# power_board1_v1_0.net
KiCad netlist of a schematic drawn in EAGLE
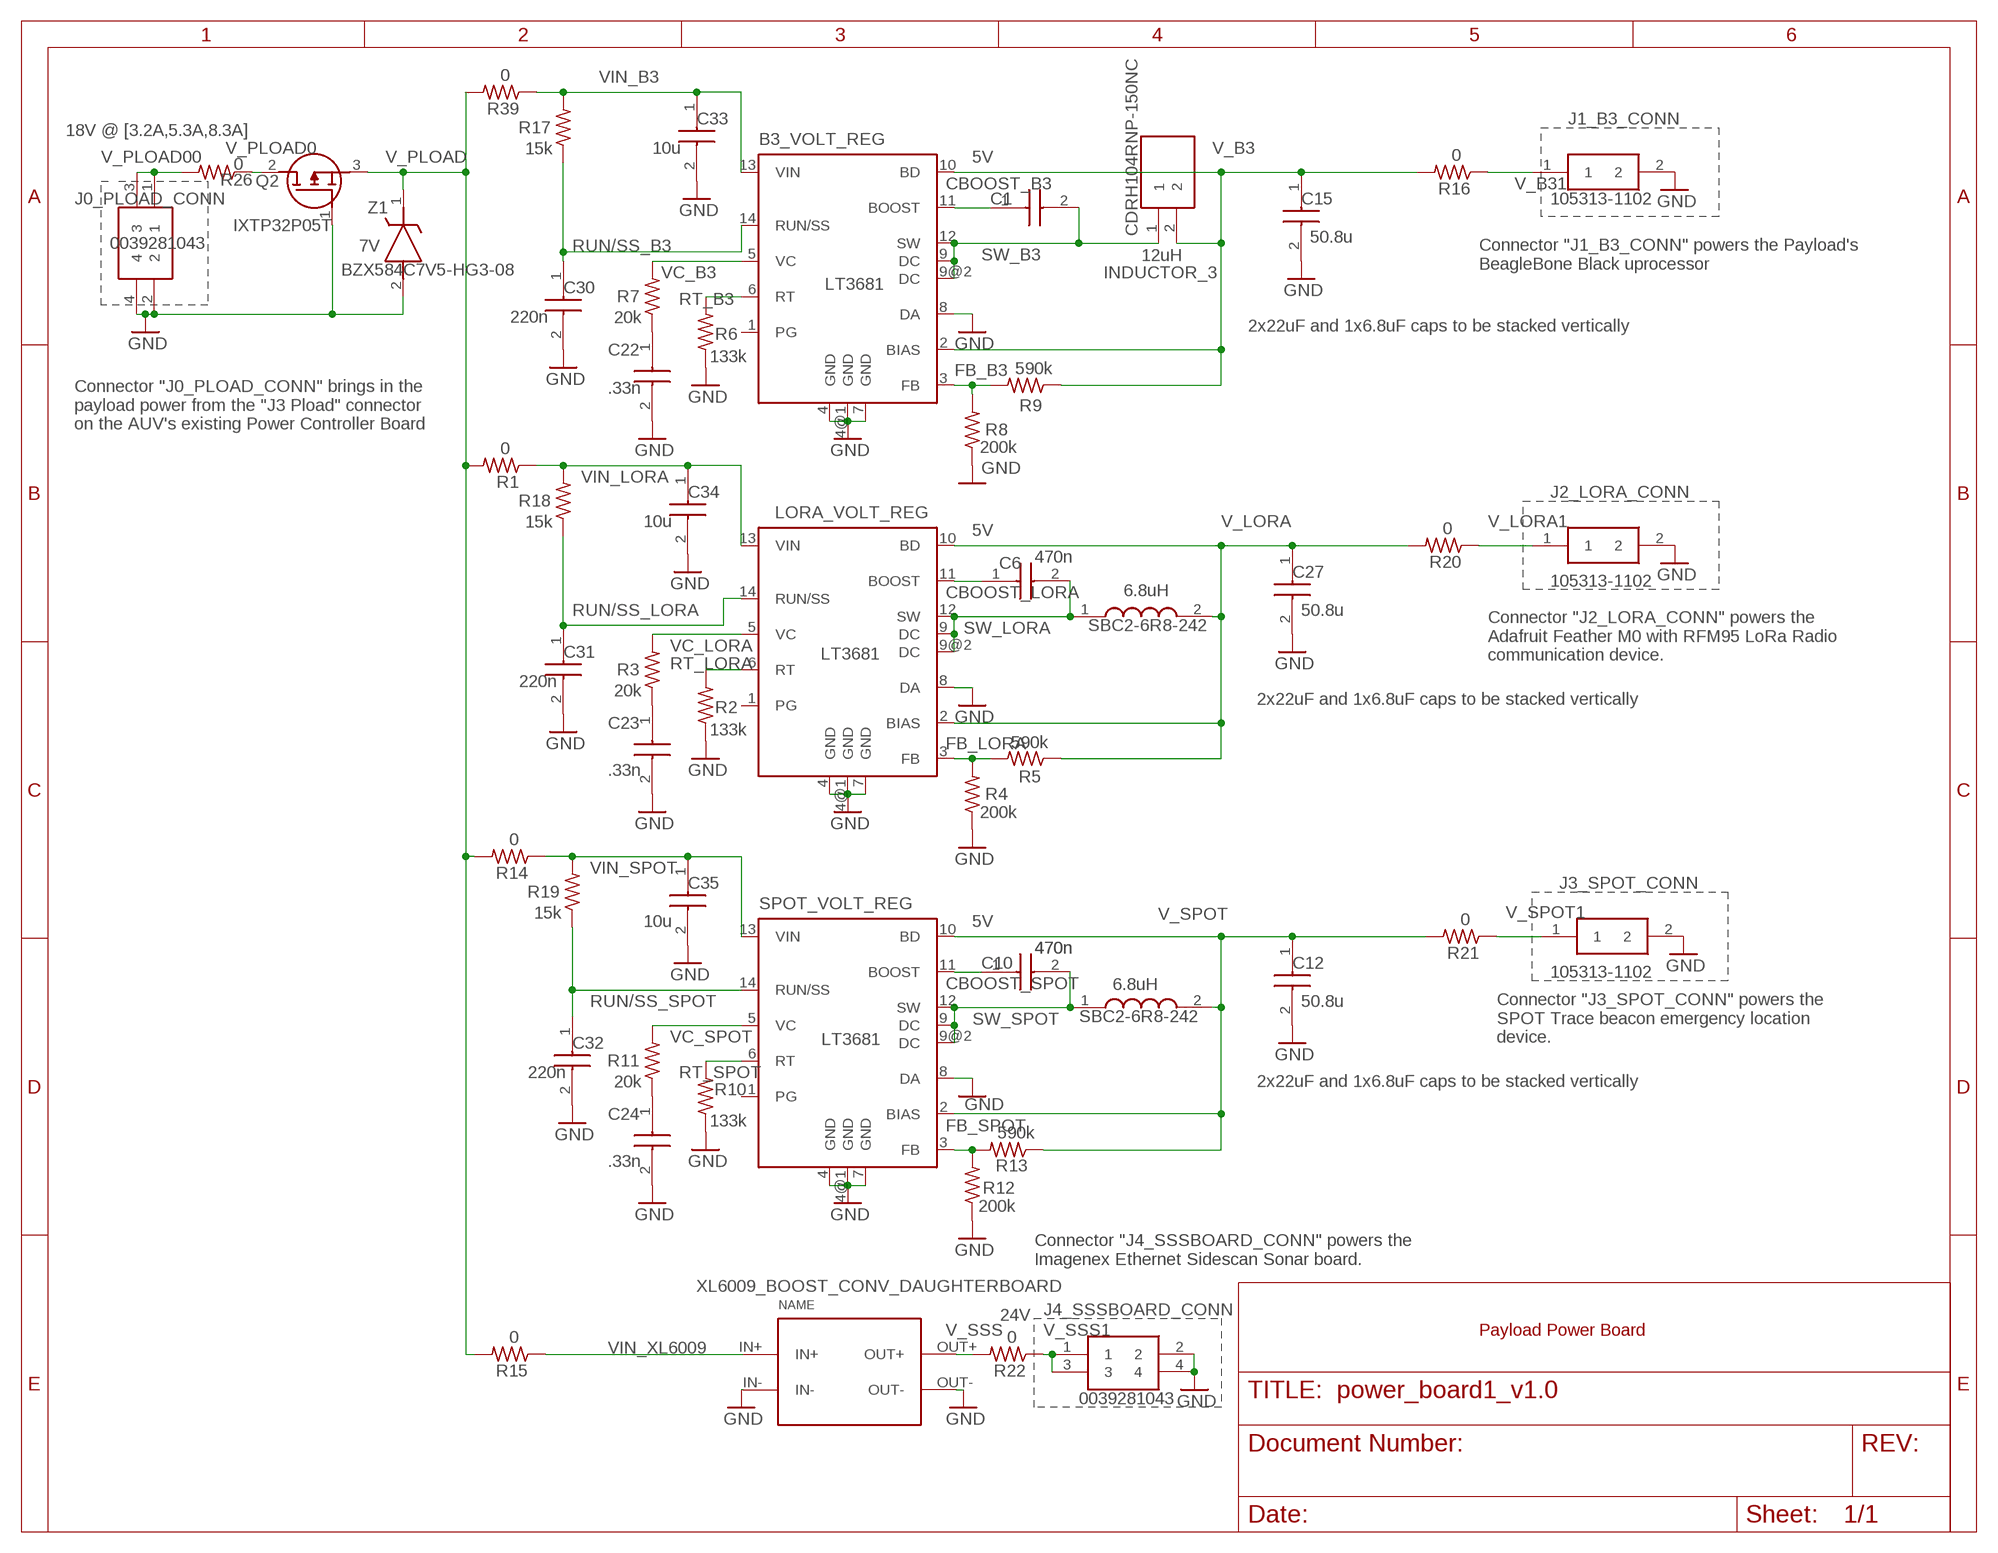
[diagram p0: schematic, sheet 1]

(export (version "E")
  (design (tool "Eeschema 10.0.6"))
  (components
    (comp (ref "B3_VOLT_REG")
      (value "LT3681")
      (footprint "eagle-import:DFN14-4X3DE")
      (fields (field (name "MPN") "LT3681EDE#PBF"))
      (libsource (lib "eagle-import") (part "LT3681"))
    )
    (comp (ref "C1")
      (value "08053C474KAT2A")
      (footprint "eagle-import:CAPC2012X140N")
      (fields
        (field (name "MOUSER_PART_NUMBER") "581-08053C474KAT2A")
        (field (name "RS_PART_NUMBER") "1747389")
      )
      (libsource (lib "eagle-import") (part "08053C474KAT2A"))
    )
    (comp (ref "C6")
      (value "08053C474KAT2A")
      (footprint "eagle-import:CAPC2012X140N")
      (fields
        (field (name "MOUSER_PART_NUMBER") "581-08053C474KAT2A")
        (field (name "RS_PART_NUMBER") "1747389")
      )
      (libsource (lib "eagle-import") (part "08053C474KAT2A"))
    )
    (comp (ref "C10")
      (value "08053C474KAT2A")
      (footprint "eagle-import:CAPC2012X140N")
      (fields
        (field (name "MOUSER_PART_NUMBER") "581-08053C474KAT2A")
        (field (name "RS_PART_NUMBER") "1747389")
      )
      (libsource (lib "eagle-import") (part "08053C474KAT2A"))
    )
    (comp (ref "C12")
      (value "12103C226KAT2A")
      (footprint "eagle-import:CAPC3225X279N")
      (fields (field (name "MOUSER_PART_NUMBER") "581-12103C226KAT2A"))
      (libsource (lib "eagle-import") (part "12103C226KAT2A"))
    )
    (comp (ref "C15")
      (value "12103C226KAT2A")
      (footprint "eagle-import:CAPC3225X279N")
      (fields (field (name "MOUSER_PART_NUMBER") "581-12103C226KAT2A"))
      (libsource (lib "eagle-import") (part "12103C226KAT2A"))
    )
    (comp (ref "C22")
      (value "08053C334KAT2A")
      (footprint "eagle-import:CAPC2012X140N")
      (fields
        (field (name "MOUSER_PART_NUMBER") "581-08053C334KAT2A")
        (field (name "RS_PART_NUMBER") "1747387")
      )
      (libsource (lib "eagle-import") (part "08053C334KAT2A"))
    )
    (comp (ref "C23")
      (value "08053C334KAT2A")
      (footprint "eagle-import:CAPC2012X140N")
      (fields
        (field (name "MOUSER_PART_NUMBER") "581-08053C334KAT2A")
        (field (name "RS_PART_NUMBER") "1747387")
      )
      (libsource (lib "eagle-import") (part "08053C334KAT2A"))
    )
    (comp (ref "C24")
      (value "08053C334KAT2A")
      (footprint "eagle-import:CAPC2012X140N")
      (fields
        (field (name "MOUSER_PART_NUMBER") "581-08053C334KAT2A")
        (field (name "RS_PART_NUMBER") "1747387")
      )
      (libsource (lib "eagle-import") (part "08053C334KAT2A"))
    )
    (comp (ref "C27")
      (value "12103C226KAT2A")
      (footprint "eagle-import:CAPC3225X279N")
      (fields (field (name "MOUSER_PART_NUMBER") "581-12103C226KAT2A"))
      (libsource (lib "eagle-import") (part "12103C226KAT2A"))
    )
    (comp (ref "C30")
      (value "08051C224KAT2A")
      (footprint "eagle-import:CAPC2012X140N")
      (fields (field (name "MOUSER_PART_NUMBER") "581-08051C224KAT2A"))
      (libsource (lib "eagle-import") (part "08051C224KAT2A"))
    )
    (comp (ref "C31")
      (value "08051C224KAT2A")
      (footprint "eagle-import:CAPC2012X140N")
      (fields (field (name "MOUSER_PART_NUMBER") "581-08051C224KAT2A"))
      (libsource (lib "eagle-import") (part "08051C224KAT2A"))
    )
    (comp (ref "C32")
      (value "08051C224KAT2A")
      (footprint "eagle-import:CAPC2012X140N")
      (fields (field (name "MOUSER_PART_NUMBER") "581-08051C224KAT2A"))
      (libsource (lib "eagle-import") (part "08051C224KAT2A"))
    )
    (comp (ref "C33")
      (value "22201C106KAT2A")
      (footprint "eagle-import:CAPC5750X279N")
      (fields (field (name "MOUSER_PART_NUMBER") "581-22201C106KAT2A"))
      (libsource (lib "eagle-import") (part "22201C106KAT2A"))
    )
    (comp (ref "C34")
      (value "22201C106KAT2A")
      (footprint "eagle-import:CAPC5750X279N")
      (fields (field (name "MOUSER_PART_NUMBER") "581-22201C106KAT2A"))
      (libsource (lib "eagle-import") (part "22201C106KAT2A"))
    )
    (comp (ref "C35")
      (value "22201C106KAT2A")
      (footprint "eagle-import:CAPC5750X279N")
      (fields (field (name "MOUSER_PART_NUMBER") "581-22201C106KAT2A"))
      (libsource (lib "eagle-import") (part "22201C106KAT2A"))
    )
    (comp (ref "INDUCTOR_3")
      (value "CDRH104RNP-150NC")
      (footprint "eagle-import:INDPM102100X400N")
      (fields (field (name "MOUSER_PART_NUMBER") "851-CDRH104RNP-150NC"))
      (libsource (lib "eagle-import") (part "CDRH104RNP-150NC"))
    )
    (comp (ref "J0_PLOAD_CONN")
      (value "0039281043")
      (footprint "eagle-import:SHDR4W125P550X420_2X2_960X960X")
      (libsource (lib "eagle-import") (part "0039281043"))
    )
    (comp (ref "J1_B3_CONN")
      (value "105313-1102")
      (footprint "eagle-import:1053131102")
      (fields (field (name "MOUSER_PART_NUMBER") "538-105313-1102") (field (name "RS_PART_NUMBER") "1623686"))
      (libsource (lib "eagle-import") (part "105313-1102"))
    )
    (comp (ref "J2_LORA_CONN")
      (value "105313-1102")
      (footprint "eagle-import:1053131102")
      (fields (field (name "MOUSER_PART_NUMBER") "538-105313-1102") (field (name "RS_PART_NUMBER") "1623686"))
      (libsource (lib "eagle-import") (part "105313-1102"))
    )
    (comp (ref "J3_SPOT_CONN")
      (value "105313-1102")
      (footprint "eagle-import:1053131102")
      (fields (field (name "MOUSER_PART_NUMBER") "538-105313-1102") (field (name "RS_PART_NUMBER") "1623686"))
      (libsource (lib "eagle-import") (part "105313-1102"))
    )
    (comp (ref "J4_SSSBOARD_CONN")
      (value "0039281043")
      (footprint "eagle-import:SHDR4W125P550X420_2X2_960X960X")
      (libsource (lib "eagle-import") (part "0039281043"))
    )
    (comp (ref "L4")
      (value "SBC2-6R8-242")
      (footprint "eagle-import:SBC26R8242")
      (fields (field (name "MOUSER_PART_NUMBER") "80-SBC2-6R8-242"))
      (libsource (lib "eagle-import") (part "SBC2-6R8-242"))
    )
    (comp (ref "L5")
      (value "SBC2-6R8-242")
      (footprint "eagle-import:SBC26R8242")
      (fields (field (name "MOUSER_PART_NUMBER") "80-SBC2-6R8-242"))
      (libsource (lib "eagle-import") (part "SBC2-6R8-242"))
    )
    (comp (ref "LORA_VOLT_REG")
      (value "LT3681")
      (footprint "eagle-import:DFN14-4X3DE")
      (fields (field (name "MPN") "LT3681EDE#PBF"))
      (libsource (lib "eagle-import") (part "LT3681"))
    )
    (comp (ref "Q2")
      (value "IXTP32P05T")
      (footprint "eagle-import:TO254P470X1001X2012-3P")
      (fields (field (name "MOUSER_PART_NUMBER") "747-IXTP32P05T"))
      (libsource (lib "eagle-import") (part "IXTP32P05T"))
    )
    (comp (ref "R1")
      (value "0")
      (footprint "eagle-import:0207_2V")
      (fields (field (name "MFR") "Yageo") (field (name "MPN") "RC0805FR-0710KL"))
      (libsource (lib "eagle-import") (part "R-US_0207/2V"))
    )
    (comp (ref "R2")
      (value "133k")
      (footprint "eagle-import:R0805")
      (libsource (lib "eagle-import") (part "R-US_R0805"))
    )
    (comp (ref "R3")
      (value "20k")
      (footprint "eagle-import:R0805")
      (libsource (lib "eagle-import") (part "R-US_R0805"))
    )
    (comp (ref "R4")
      (value "200k")
      (footprint "eagle-import:R0805")
      (libsource (lib "eagle-import") (part "R-US_R0805"))
    )
    (comp (ref "R5")
      (value "590k")
      (footprint "eagle-import:R0805")
      (libsource (lib "eagle-import") (part "R-US_R0805"))
    )
    (comp (ref "R6")
      (value "133k")
      (footprint "eagle-import:R0805")
      (libsource (lib "eagle-import") (part "R-US_R0805"))
    )
    (comp (ref "R7")
      (value "20k")
      (footprint "eagle-import:R0805")
      (libsource (lib "eagle-import") (part "R-US_R0805"))
    )
    (comp (ref "R8")
      (value "200k")
      (footprint "eagle-import:R0805")
      (libsource (lib "eagle-import") (part "R-US_R0805"))
    )
    (comp (ref "R9")
      (value "590k")
      (footprint "eagle-import:R0805")
      (libsource (lib "eagle-import") (part "R-US_R0805"))
    )
    (comp (ref "R10")
      (value "133k")
      (footprint "eagle-import:R0805")
      (libsource (lib "eagle-import") (part "R-US_R0805"))
    )
    (comp (ref "R11")
      (value "20k")
      (footprint "eagle-import:R0805")
      (libsource (lib "eagle-import") (part "R-US_R0805"))
    )
    (comp (ref "R12")
      (value "200k")
      (footprint "eagle-import:R0805")
      (libsource (lib "eagle-import") (part "R-US_R0805"))
    )
    (comp (ref "R13")
      (value "590k")
      (footprint "eagle-import:R0805")
      (libsource (lib "eagle-import") (part "R-US_R0805"))
    )
    (comp (ref "R14")
      (value "0")
      (footprint "eagle-import:0207_2V")
      (fields (field (name "MFR") "Yageo") (field (name "MPN") "RC0805FR-0710KL"))
      (libsource (lib "eagle-import") (part "R-US_0207/2V"))
    )
    (comp (ref "R15")
      (value "0")
      (footprint "eagle-import:0207_2V")
      (fields (field (name "MFR") "Yageo") (field (name "MPN") "RC0805FR-0710KL"))
      (libsource (lib "eagle-import") (part "R-US_0207/2V"))
    )
    (comp (ref "R16")
      (value "0")
      (footprint "eagle-import:0207_2V")
      (fields (field (name "MFR") "Yageo") (field (name "MPN") "RC0805FR-0710KL"))
      (libsource (lib "eagle-import") (part "R-US_0207/2V"))
    )
    (comp (ref "R17")
      (value "15k")
      (footprint "eagle-import:R0805")
      (libsource (lib "eagle-import") (part "R-US_R0805"))
    )
    (comp (ref "R18")
      (value "15k")
      (footprint "eagle-import:R0805")
      (libsource (lib "eagle-import") (part "R-US_R0805"))
    )
    (comp (ref "R19")
      (value "15k")
      (footprint "eagle-import:R0805")
      (libsource (lib "eagle-import") (part "R-US_R0805"))
    )
    (comp (ref "R20")
      (value "0")
      (footprint "eagle-import:0207_2V")
      (fields (field (name "MFR") "Yageo") (field (name "MPN") "RC0805FR-0710KL"))
      (libsource (lib "eagle-import") (part "R-US_0207/2V"))
    )
    (comp (ref "R21")
      (value "0")
      (footprint "eagle-import:0207_2V")
      (fields (field (name "MFR") "Yageo") (field (name "MPN") "RC0805FR-0710KL"))
      (libsource (lib "eagle-import") (part "R-US_0207/2V"))
    )
    (comp (ref "R22")
      (value "0")
      (footprint "eagle-import:0207_2V")
      (fields (field (name "MFR") "Yageo") (field (name "MPN") "RC0805FR-0710KL"))
      (libsource (lib "eagle-import") (part "R-US_0207/2V"))
    )
    (comp (ref "R26")
      (value "0")
      (footprint "eagle-import:0207_2V")
      (fields (field (name "MFR") "Yageo") (field (name "MPN") "RC0805FR-0710KL"))
      (libsource (lib "eagle-import") (part "R-US_0207/2V"))
    )
    (comp (ref "R39")
      (value "0")
      (footprint "eagle-import:0207_2V")
      (fields (field (name "MFR") "Yageo") (field (name "MPN") "RC0805FR-0710KL"))
      (libsource (lib "eagle-import") (part "R-US_0207/2V"))
    )
    (comp (ref "SPOT_VOLT_REG")
      (value "LT3681")
      (footprint "eagle-import:DFN14-4X3DE")
      (fields (field (name "MPN") "LT3681EDE#PBF"))
      (libsource (lib "eagle-import") (part "LT3681"))
    )
    (comp (ref "XL6009_BOOST_CONV_DAUGHTERBOARD")
      (value "CP8-ADJ")
      (footprint "eagle-import:CP8-ADJ")
      (libsource (lib "eagle-import") (part "CP8-ADJ"))
    )
    (comp (ref "Z1")
      (value "BZX584C7V5-HG3-08")
      (footprint "eagle-import:SODFL1608X75N")
      (fields (field (name "MOUSER_PART_NUMBER") "78-BZX584C7V5-HG3-08"))
      (libsource (lib "eagle-import") (part "BZX584C7V5-HG3-08"))
    )
  )
  (nets
    (net (code "1") (name "/CBOOST_B3") (class "Default")
      (node (ref "B3_VOLT_REG") (pin "11") (pinfunction "BOOST_11") (pintype "output"))
      (node (ref "C1") (pin "1") (pinfunction "1_1") (pintype "bidirectional"))
    )
    (net (code "2") (name "/CBOOST_LORA") (class "Default")
      (node (ref "C6") (pin "1") (pinfunction "1_1") (pintype "bidirectional"))
      (node (ref "LORA_VOLT_REG") (pin "11") (pinfunction "BOOST_11") (pintype "output"))
    )
    (net (code "3") (name "/CBOOST_SPOT") (class "Default")
      (node (ref "C10") (pin "1") (pinfunction "1_1") (pintype "bidirectional"))
      (node (ref "SPOT_VOLT_REG") (pin "11") (pinfunction "BOOST_11") (pintype "output"))
    )
    (net (code "4") (name "/FB_B3") (class "Default")
      (node (ref "B3_VOLT_REG") (pin "3") (pinfunction "FB_3") (pintype "input"))
      (node (ref "R8") (pin "2") (pinfunction "2_2") (pintype "passive"))
      (node (ref "R9") (pin "2") (pinfunction "2_2") (pintype "passive"))
    )
    (net (code "5") (name "/FB_LORA") (class "Default")
      (node (ref "LORA_VOLT_REG") (pin "3") (pinfunction "FB_3") (pintype "input"))
      (node (ref "R4") (pin "2") (pinfunction "2_2") (pintype "passive"))
      (node (ref "R5") (pin "2") (pinfunction "2_2") (pintype "passive"))
    )
    (net (code "6") (name "/FB_SPOT") (class "Default")
      (node (ref "R12") (pin "2") (pinfunction "2_2") (pintype "passive"))
      (node (ref "R13") (pin "2") (pinfunction "2_2") (pintype "passive"))
      (node (ref "SPOT_VOLT_REG") (pin "3") (pinfunction "FB_3") (pintype "input"))
    )
    (net (code "7") (name "/RT_B3") (class "Default")
      (node (ref "B3_VOLT_REG") (pin "6") (pinfunction "RT_6") (pintype "input"))
      (node (ref "R6") (pin "2") (pinfunction "2_2") (pintype "passive"))
    )
    (net (code "8") (name "/RT_LORA") (class "Default")
      (node (ref "LORA_VOLT_REG") (pin "6") (pinfunction "RT_6") (pintype "input"))
      (node (ref "R2") (pin "2") (pinfunction "2_2") (pintype "passive"))
    )
    (net (code "9") (name "/RT_SPOT") (class "Default")
      (node (ref "R10") (pin "2") (pinfunction "2_2") (pintype "passive"))
      (node (ref "SPOT_VOLT_REG") (pin "6") (pinfunction "RT_6") (pintype "input"))
    )
    (net (code "10") (name "/RUN{slash}SS_B3") (class "Default")
      (node (ref "B3_VOLT_REG") (pin "14") (pinfunction "RUN/SS_14") (pintype "input"))
      (node (ref "C30") (pin "1") (pinfunction "1_1") (pintype "bidirectional"))
      (node (ref "R17") (pin "1") (pinfunction "1_1") (pintype "passive"))
    )
    (net (code "11") (name "/RUN{slash}SS_LORA") (class "Default")
      (node (ref "C31") (pin "1") (pinfunction "1_1") (pintype "bidirectional"))
      (node (ref "LORA_VOLT_REG") (pin "14") (pinfunction "RUN/SS_14") (pintype "input"))
      (node (ref "R18") (pin "1") (pinfunction "1_1") (pintype "passive"))
    )
    (net (code "12") (name "/RUN{slash}SS_SPOT") (class "Default")
      (node (ref "C32") (pin "1") (pinfunction "1_1") (pintype "bidirectional"))
      (node (ref "R19") (pin "1") (pinfunction "1_1") (pintype "passive"))
      (node (ref "SPOT_VOLT_REG") (pin "14") (pinfunction "RUN/SS_14") (pintype "input"))
    )
    (net (code "13") (name "/SW_B3") (class "Default")
      (node (ref "B3_VOLT_REG") (pin "12") (pinfunction "SW_12") (pintype "output"))
      (node (ref "B3_VOLT_REG") (pin "9") (pinfunction "DC_9") (pintype "passive"))
      (node (ref "B3_VOLT_REG") (pin "9@2") (pinfunction "DC_9@2") (pintype "passive"))
      (node (ref "C1") (pin "2") (pinfunction "2_2") (pintype "bidirectional"))
      (node (ref "INDUCTOR_3") (pin "1") (pinfunction "1_1") (pintype "bidirectional"))
    )
    (net (code "14") (name "/SW_LORA") (class "Default")
      (node (ref "C6") (pin "2") (pinfunction "2_2") (pintype "bidirectional"))
      (node (ref "L5") (pin "1") (pinfunction "1_1") (pintype "bidirectional"))
      (node (ref "LORA_VOLT_REG") (pin "12") (pinfunction "SW_12") (pintype "output"))
      (node (ref "LORA_VOLT_REG") (pin "9") (pinfunction "DC_9") (pintype "passive"))
      (node (ref "LORA_VOLT_REG") (pin "9@2") (pinfunction "DC_9@2") (pintype "passive"))
    )
    (net (code "15") (name "/SW_SPOT") (class "Default")
      (node (ref "C10") (pin "2") (pinfunction "2_2") (pintype "bidirectional"))
      (node (ref "L4") (pin "1") (pinfunction "1_1") (pintype "bidirectional"))
      (node (ref "SPOT_VOLT_REG") (pin "12") (pinfunction "SW_12") (pintype "output"))
      (node (ref "SPOT_VOLT_REG") (pin "9") (pinfunction "DC_9") (pintype "passive"))
      (node (ref "SPOT_VOLT_REG") (pin "9@2") (pinfunction "DC_9@2") (pintype "passive"))
    )
    (net (code "16") (name "/VC_B3") (class "Default")
      (node (ref "B3_VOLT_REG") (pin "5") (pinfunction "VC_5") (pintype "output"))
      (node (ref "R7") (pin "2") (pinfunction "2_2") (pintype "passive"))
    )
    (net (code "17") (name "/VC_LORA") (class "Default")
      (node (ref "LORA_VOLT_REG") (pin "5") (pinfunction "VC_5") (pintype "output"))
      (node (ref "R3") (pin "2") (pinfunction "2_2") (pintype "passive"))
    )
    (net (code "18") (name "/VC_SPOT") (class "Default")
      (node (ref "R11") (pin "2") (pinfunction "2_2") (pintype "passive"))
      (node (ref "SPOT_VOLT_REG") (pin "5") (pinfunction "VC_5") (pintype "output"))
    )
    (net (code "19") (name "/VIN_B3") (class "Default")
      (node (ref "B3_VOLT_REG") (pin "13") (pinfunction "VIN_13") (pintype "input"))
      (node (ref "C33") (pin "1") (pinfunction "1_1") (pintype "bidirectional"))
      (node (ref "R17") (pin "2") (pinfunction "2_2") (pintype "passive"))
      (node (ref "R39") (pin "1") (pinfunction "1_1") (pintype "passive"))
    )
    (net (code "20") (name "/VIN_LORA") (class "Default")
      (node (ref "C34") (pin "1") (pinfunction "1_1") (pintype "bidirectional"))
      (node (ref "LORA_VOLT_REG") (pin "13") (pinfunction "VIN_13") (pintype "input"))
      (node (ref "R1") (pin "1") (pinfunction "1_1") (pintype "passive"))
      (node (ref "R18") (pin "2") (pinfunction "2_2") (pintype "passive"))
    )
    (net (code "21") (name "/VIN_SPOT") (class "Default")
      (node (ref "C35") (pin "1") (pinfunction "1_1") (pintype "bidirectional"))
      (node (ref "R14") (pin "1") (pinfunction "1_1") (pintype "passive"))
      (node (ref "R19") (pin "2") (pinfunction "2_2") (pintype "passive"))
      (node (ref "SPOT_VOLT_REG") (pin "13") (pinfunction "VIN_13") (pintype "input"))
    )
    (net (code "22") (name "/VIN_XL6009") (class "Default")
      (node (ref "R15") (pin "1") (pinfunction "1_1") (pintype "passive"))
      (node (ref "XL6009_BOOST_CONV_DAUGHTERBOARD") (pin "IN+") (pinfunction "IN+_IN+") (pintype "passive"))
    )
    (net (code "23") (name "/V_B3") (class "Default")
      (node (ref "B3_VOLT_REG") (pin "10") (pinfunction "BD_10") (pintype "input"))
      (node (ref "B3_VOLT_REG") (pin "2") (pinfunction "BIAS_2") (pintype "input"))
      (node (ref "C15") (pin "1") (pinfunction "1_1") (pintype "bidirectional"))
      (node (ref "INDUCTOR_3") (pin "2") (pinfunction "2_2") (pintype "bidirectional"))
      (node (ref "R16") (pin "2") (pinfunction "2_2") (pintype "passive"))
      (node (ref "R9") (pin "1") (pinfunction "1_1") (pintype "passive"))
    )
    (net (code "24") (name "/V_B31") (class "Default")
      (node (ref "J1_B3_CONN") (pin "1") (pinfunction "1_1") (pintype "bidirectional"))
      (node (ref "R16") (pin "1") (pinfunction "1_1") (pintype "passive"))
    )
    (net (code "25") (name "/V_LORA") (class "Default")
      (node (ref "C27") (pin "1") (pinfunction "1_1") (pintype "bidirectional"))
      (node (ref "L5") (pin "2") (pinfunction "2_2") (pintype "bidirectional"))
      (node (ref "LORA_VOLT_REG") (pin "10") (pinfunction "BD_10") (pintype "input"))
      (node (ref "LORA_VOLT_REG") (pin "2") (pinfunction "BIAS_2") (pintype "input"))
      (node (ref "R20") (pin "2") (pinfunction "2_2") (pintype "passive"))
      (node (ref "R5") (pin "1") (pinfunction "1_1") (pintype "passive"))
    )
    (net (code "26") (name "/V_LORA1") (class "Default")
      (node (ref "J2_LORA_CONN") (pin "1") (pinfunction "1_1") (pintype "bidirectional"))
      (node (ref "R20") (pin "1") (pinfunction "1_1") (pintype "passive"))
    )
    (net (code "27") (name "/V_PLOAD") (class "Default")
      (node (ref "Q2") (pin "3") (pinfunction "S_3") (pintype "bidirectional"))
      (node (ref "R1") (pin "2") (pinfunction "2_2") (pintype "passive"))
      (node (ref "R14") (pin "2") (pinfunction "2_2") (pintype "passive"))
      (node (ref "R15") (pin "2") (pinfunction "2_2") (pintype "passive"))
      (node (ref "R39") (pin "2") (pinfunction "2_2") (pintype "passive"))
      (node (ref "Z1") (pin "1") (pinfunction "K_1") (pintype "bidirectional"))
    )
    (net (code "28") (name "/V_PLOAD0") (class "Default")
      (node (ref "Q2") (pin "2") (pinfunction "D_2") (pintype "bidirectional"))
      (node (ref "R26") (pin "1") (pinfunction "1_1") (pintype "passive"))
    )
    (net (code "29") (name "/V_PLOAD00") (class "Default")
      (node (ref "J0_PLOAD_CONN") (pin "1") (pinfunction "1_1") (pintype "bidirectional"))
      (node (ref "J0_PLOAD_CONN") (pin "3") (pinfunction "3_3") (pintype "bidirectional"))
      (node (ref "R26") (pin "2") (pinfunction "2_2") (pintype "passive"))
    )
    (net (code "30") (name "/V_SPOT") (class "Default")
      (node (ref "C12") (pin "1") (pinfunction "1_1") (pintype "bidirectional"))
      (node (ref "L4") (pin "2") (pinfunction "2_2") (pintype "bidirectional"))
      (node (ref "R13") (pin "1") (pinfunction "1_1") (pintype "passive"))
      (node (ref "R21") (pin "2") (pinfunction "2_2") (pintype "passive"))
      (node (ref "SPOT_VOLT_REG") (pin "10") (pinfunction "BD_10") (pintype "input"))
      (node (ref "SPOT_VOLT_REG") (pin "2") (pinfunction "BIAS_2") (pintype "input"))
    )
    (net (code "31") (name "/V_SPOT1") (class "Default")
      (node (ref "J3_SPOT_CONN") (pin "1") (pinfunction "1_1") (pintype "bidirectional"))
      (node (ref "R21") (pin "1") (pinfunction "1_1") (pintype "passive"))
    )
    (net (code "32") (name "/V_SSS") (class "Default")
      (node (ref "R22") (pin "2") (pinfunction "2_2") (pintype "passive"))
      (node (ref "XL6009_BOOST_CONV_DAUGHTERBOARD") (pin "OUT+") (pinfunction "OUT+_OUT+") (pintype "passive"))
    )
    (net (code "33") (name "/V_SSS1") (class "Default")
      (node (ref "J4_SSSBOARD_CONN") (pin "1") (pinfunction "1_1") (pintype "bidirectional"))
      (node (ref "J4_SSSBOARD_CONN") (pin "3") (pinfunction "3_3") (pintype "bidirectional"))
      (node (ref "R22") (pin "1") (pinfunction "1_1") (pintype "passive"))
    )
    (net (code "34") (name "GND") (class "Default")
      (node (ref "B3_VOLT_REG") (pin "4") (pinfunction "GND_4") (pintype "input"))
      (node (ref "B3_VOLT_REG") (pin "4@1") (pinfunction "GND_4@1") (pintype "input"))
      (node (ref "B3_VOLT_REG") (pin "7") (pinfunction "GND_7") (pintype "input"))
      (node (ref "B3_VOLT_REG") (pin "8") (pinfunction "DA_8") (pintype "passive"))
      (node (ref "C12") (pin "2") (pinfunction "2_2") (pintype "bidirectional"))
      (node (ref "C15") (pin "2") (pinfunction "2_2") (pintype "bidirectional"))
      (node (ref "C22") (pin "2") (pinfunction "2_2") (pintype "bidirectional"))
      (node (ref "C23") (pin "2") (pinfunction "2_2") (pintype "bidirectional"))
      (node (ref "C24") (pin "2") (pinfunction "2_2") (pintype "bidirectional"))
      (node (ref "C27") (pin "2") (pinfunction "2_2") (pintype "bidirectional"))
      (node (ref "C30") (pin "2") (pinfunction "2_2") (pintype "bidirectional"))
      (node (ref "C31") (pin "2") (pinfunction "2_2") (pintype "bidirectional"))
      (node (ref "C32") (pin "2") (pinfunction "2_2") (pintype "bidirectional"))
      (node (ref "C33") (pin "2") (pinfunction "2_2") (pintype "bidirectional"))
      (node (ref "C34") (pin "2") (pinfunction "2_2") (pintype "bidirectional"))
      (node (ref "C35") (pin "2") (pinfunction "2_2") (pintype "bidirectional"))
      (node (ref "J0_PLOAD_CONN") (pin "2") (pinfunction "2_2") (pintype "bidirectional"))
      (node (ref "J0_PLOAD_CONN") (pin "4") (pinfunction "4_4") (pintype "bidirectional"))
      (node (ref "J1_B3_CONN") (pin "2") (pinfunction "2_2") (pintype "bidirectional"))
      (node (ref "J2_LORA_CONN") (pin "2") (pinfunction "2_2") (pintype "bidirectional"))
      (node (ref "J3_SPOT_CONN") (pin "2") (pinfunction "2_2") (pintype "bidirectional"))
      (node (ref "J4_SSSBOARD_CONN") (pin "2") (pinfunction "2_2") (pintype "bidirectional"))
      (node (ref "J4_SSSBOARD_CONN") (pin "4") (pinfunction "4_4") (pintype "bidirectional"))
      (node (ref "LORA_VOLT_REG") (pin "4") (pinfunction "GND_4") (pintype "input"))
      (node (ref "LORA_VOLT_REG") (pin "4@1") (pinfunction "GND_4@1") (pintype "input"))
      (node (ref "LORA_VOLT_REG") (pin "7") (pinfunction "GND_7") (pintype "input"))
      (node (ref "LORA_VOLT_REG") (pin "8") (pinfunction "DA_8") (pintype "passive"))
      (node (ref "Q2") (pin "1") (pinfunction "G_1") (pintype "bidirectional"))
      (node (ref "R10") (pin "1") (pinfunction "1_1") (pintype "passive"))
      (node (ref "R12") (pin "1") (pinfunction "1_1") (pintype "passive"))
      (node (ref "R2") (pin "1") (pinfunction "1_1") (pintype "passive"))
      (node (ref "R4") (pin "1") (pinfunction "1_1") (pintype "passive"))
      (node (ref "R6") (pin "1") (pinfunction "1_1") (pintype "passive"))
      (node (ref "R8") (pin "1") (pinfunction "1_1") (pintype "passive"))
      (node (ref "SPOT_VOLT_REG") (pin "4") (pinfunction "GND_4") (pintype "input"))
      (node (ref "SPOT_VOLT_REG") (pin "4@1") (pinfunction "GND_4@1") (pintype "input"))
      (node (ref "SPOT_VOLT_REG") (pin "7") (pinfunction "GND_7") (pintype "input"))
      (node (ref "SPOT_VOLT_REG") (pin "8") (pinfunction "DA_8") (pintype "passive"))
      (node (ref "XL6009_BOOST_CONV_DAUGHTERBOARD") (pin "IN-") (pinfunction "IN-_IN-") (pintype "passive"))
      (node (ref "XL6009_BOOST_CONV_DAUGHTERBOARD") (pin "OUT-") (pinfunction "OUT-_OUT-") (pintype "passive"))
      (node (ref "Z1") (pin "2") (pinfunction "A_2") (pintype "bidirectional"))
    )
    (net (code "35") (name "Net-(C22-Pad1)") (class "Default")
      (node (ref "C22") (pin "1") (pinfunction "1_1") (pintype "bidirectional"))
      (node (ref "R7") (pin "1") (pinfunction "1_1") (pintype "passive"))
    )
    (net (code "36") (name "Net-(C23-Pad1)") (class "Default")
      (node (ref "C23") (pin "1") (pinfunction "1_1") (pintype "bidirectional"))
      (node (ref "R3") (pin "1") (pinfunction "1_1") (pintype "passive"))
    )
    (net (code "37") (name "Net-(C24-Pad1)") (class "Default")
      (node (ref "C24") (pin "1") (pinfunction "1_1") (pintype "bidirectional"))
      (node (ref "R11") (pin "1") (pinfunction "1_1") (pintype "passive"))
    )
    (net (code "38") (name "unconnected-(B3_VOLT_REG-PG-Pad1)") (class "Default")
      (node (ref "B3_VOLT_REG") (pin "1") (pinfunction "PG_1") (pintype "open_collector"))
    )
    (net (code "39") (name "unconnected-(LORA_VOLT_REG-PG-Pad1)") (class "Default")
      (node (ref "LORA_VOLT_REG") (pin "1") (pinfunction "PG_1") (pintype "open_collector"))
    )
    (net (code "40") (name "unconnected-(SPOT_VOLT_REG-PG-Pad1)") (class "Default")
      (node (ref "SPOT_VOLT_REG") (pin "1") (pinfunction "PG_1") (pintype "open_collector"))
    )
  )
)
